# main_pcb.net
KiCad netlist of a schematic drawn in EAGLE
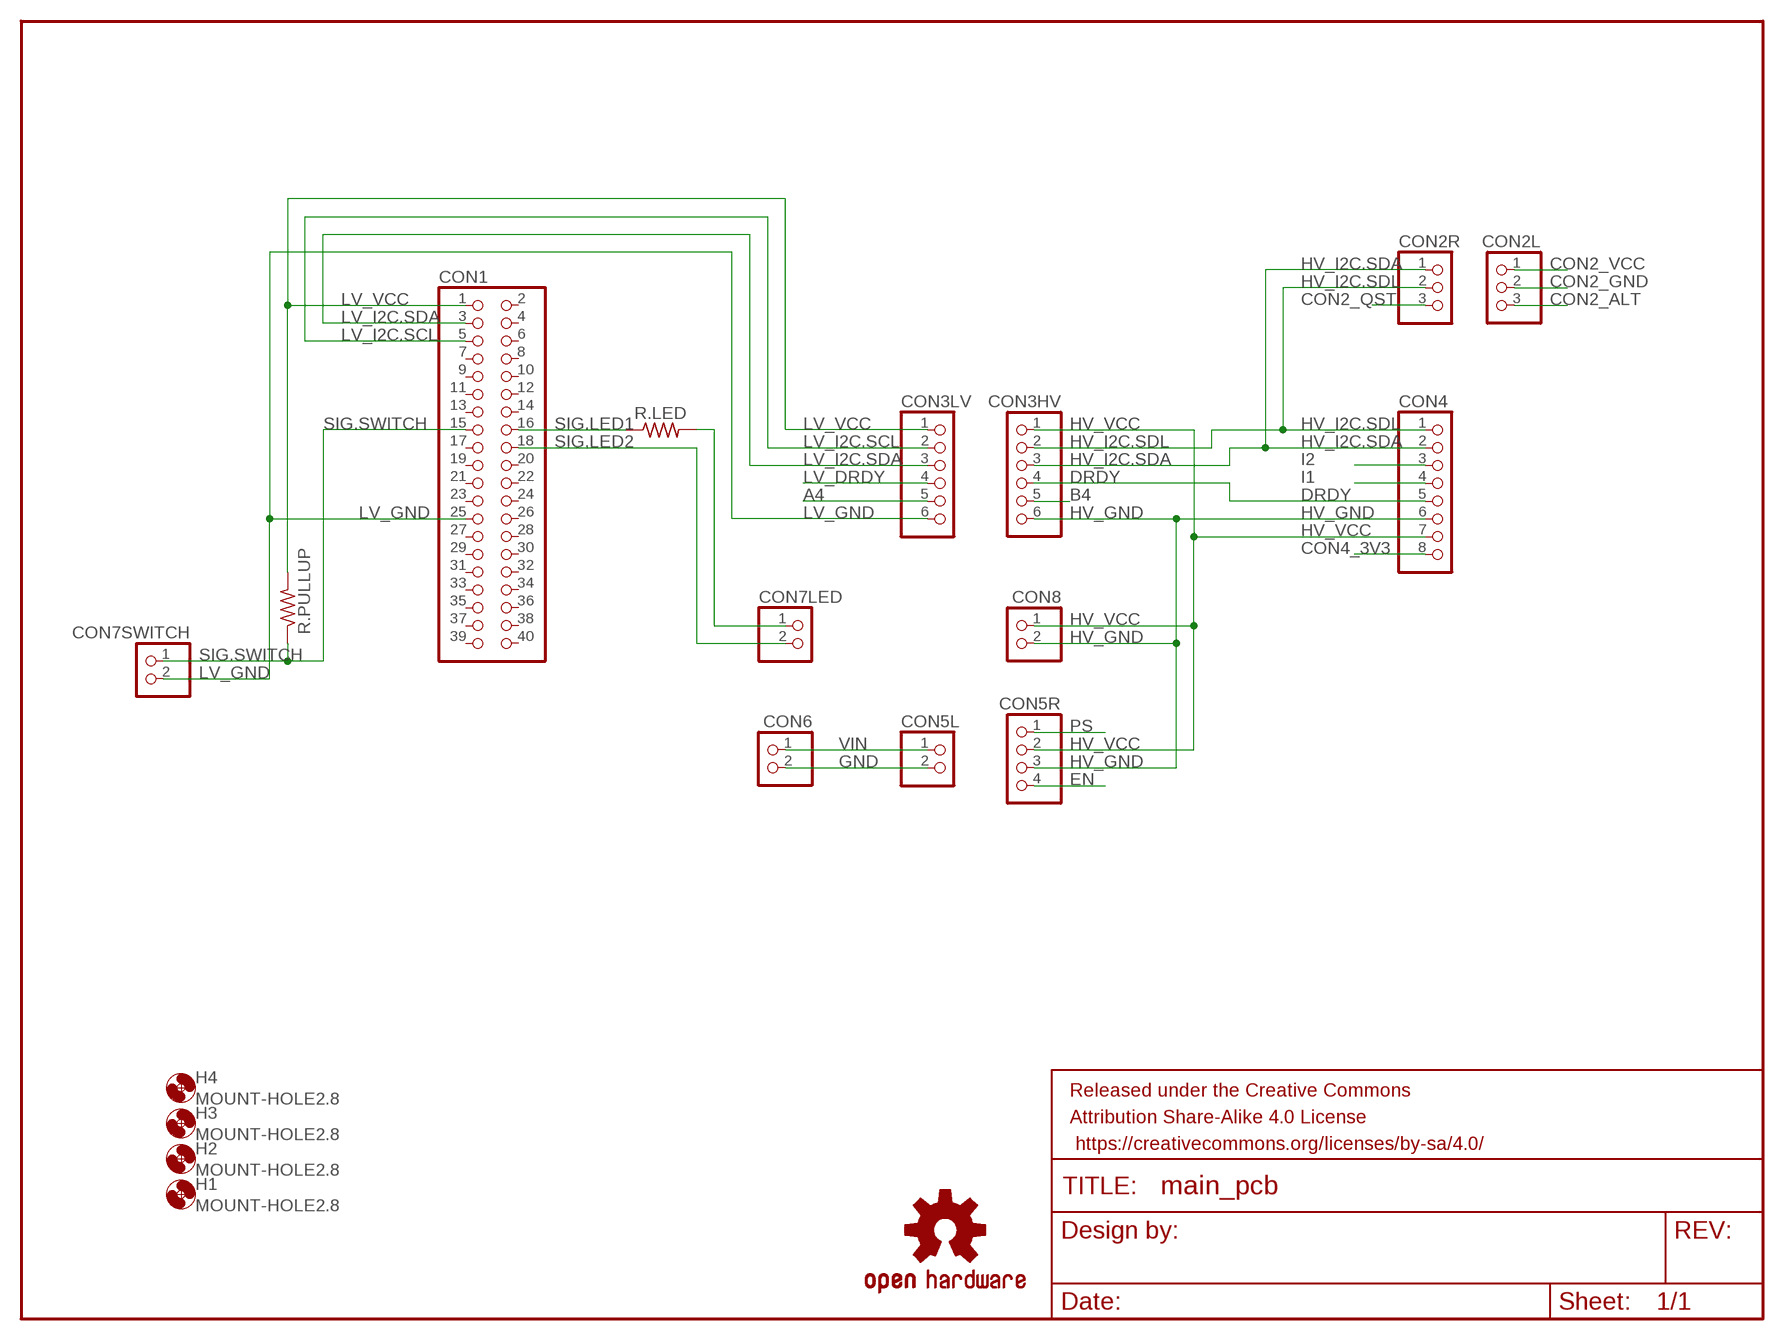
[diagram p0: schematic, sheet 1]

(export (version "E")
  (design (tool "Eeschema 10.0.6"))
  (components
    (comp (ref "CON1")
      (value "PINHD-2X20")
      (footprint "eagle-import:2X20")
      (libsource (lib "eagle-import") (part "PINHD-2X20"))
    )
    (comp (ref "CON2L")
      (value "PINHD-1X3")
      (footprint "eagle-import:1X03")
      (libsource (lib "eagle-import") (part "PINHD-1X3"))
    )
    (comp (ref "CON2R")
      (value "PINHD-1X3")
      (footprint "eagle-import:1X03")
      (libsource (lib "eagle-import") (part "PINHD-1X3"))
    )
    (comp (ref "CON3HV")
      (value "PINHD-1X6")
      (footprint "eagle-import:1X06")
      (libsource (lib "eagle-import") (part "PINHD-1X6"))
    )
    (comp (ref "CON3LV")
      (value "PINHD-1X6")
      (footprint "eagle-import:1X06")
      (libsource (lib "eagle-import") (part "PINHD-1X6"))
    )
    (comp (ref "CON4")
      (value "PINHD-1X8")
      (footprint "eagle-import:1X08")
      (libsource (lib "eagle-import") (part "PINHD-1X8"))
    )
    (comp (ref "CON5L")
      (value "PINHD-1X2")
      (footprint "eagle-import:1X02")
      (libsource (lib "eagle-import") (part "PINHD-1X2"))
    )
    (comp (ref "CON5R")
      (value "PINHD-1X4")
      (footprint "eagle-import:1X04")
      (libsource (lib "eagle-import") (part "PINHD-1X4"))
    )
    (comp (ref "CON6")
      (value "PINHD-1X2")
      (footprint "eagle-import:1X02")
      (libsource (lib "eagle-import") (part "PINHD-1X2"))
    )
    (comp (ref "CON7LED")
      (value "PINHD-1X2")
      (footprint "eagle-import:1X02")
      (libsource (lib "eagle-import") (part "PINHD-1X2"))
    )
    (comp (ref "CON7SWITCH")
      (value "PINHD-1X2")
      (footprint "eagle-import:1X02")
      (libsource (lib "eagle-import") (part "PINHD-1X2"))
    )
    (comp (ref "CON8")
      (value "PINHD-1X2")
      (footprint "eagle-import:1X02")
      (libsource (lib "eagle-import") (part "PINHD-1X2"))
    )
    (comp (ref "FRAME1")
      (value "FRAME-LETTER")
      (footprint "eagle-import:CREATIVE_COMMONS")
      (libsource (lib "eagle-import") (part "FRAME-LETTER"))
    )
    (comp (ref "H1")
      (value "MOUNT-HOLE2.8")
      (footprint "eagle-import:2,8")
      (libsource (lib "eagle-import") (part "MOUNT-HOLE2.8"))
    )
    (comp (ref "H2")
      (value "MOUNT-HOLE2.8")
      (footprint "eagle-import:2,8")
      (libsource (lib "eagle-import") (part "MOUNT-HOLE2.8"))
    )
    (comp (ref "H3")
      (value "MOUNT-HOLE2.8")
      (footprint "eagle-import:2,8")
      (libsource (lib "eagle-import") (part "MOUNT-HOLE2.8"))
    )
    (comp (ref "H4")
      (value "MOUNT-HOLE2.8")
      (footprint "eagle-import:2,8")
      (libsource (lib "eagle-import") (part "MOUNT-HOLE2.8"))
    )
    (comp (ref "LOGO1")
      (value "OSHW-LOGOL")
      (footprint "eagle-import:OSHW-LOGO-L")
      (libsource (lib "eagle-import") (part "OSHW-LOGOL"))
    )
    (comp (ref "R.LED")
      (value "R-US_0204/2V")
      (footprint "eagle-import:0204V")
      (libsource (lib "eagle-import") (part "R-US_0204/2V"))
    )
    (comp (ref "R.PULLUP")
      (value "R-US_0204/2V")
      (footprint "eagle-import:0204V")
      (libsource (lib "eagle-import") (part "R-US_0204/2V"))
    )
  )
  (nets
    (net (code "1") (name "/A4") (class "Default")
      (node (ref "CON3LV") (pin "5") (pinfunction "5_5") (pintype "passive"))
    )
    (net (code "2") (name "/B4") (class "Default")
      (node (ref "CON3HV") (pin "5") (pinfunction "5_5") (pintype "passive"))
    )
    (net (code "3") (name "/CON2_ALT") (class "Default")
      (node (ref "CON2L") (pin "3") (pinfunction "3_3") (pintype "passive"))
    )
    (net (code "4") (name "/CON2_GND") (class "Default")
      (node (ref "CON2L") (pin "2") (pinfunction "2_2") (pintype "passive"))
    )
    (net (code "5") (name "/CON2_QST") (class "Default")
      (node (ref "CON2R") (pin "3") (pinfunction "3_3") (pintype "passive"))
    )
    (net (code "6") (name "/CON2_VCC") (class "Default")
      (node (ref "CON2L") (pin "1") (pinfunction "1_1") (pintype "passive"))
    )
    (net (code "7") (name "/CON4_3V3") (class "Default")
      (node (ref "CON4") (pin "8") (pinfunction "8_8") (pintype "passive"))
    )
    (net (code "8") (name "/DRDY") (class "Default")
      (node (ref "CON3HV") (pin "4") (pinfunction "4_4") (pintype "passive"))
      (node (ref "CON4") (pin "5") (pinfunction "5_5") (pintype "passive"))
    )
    (net (code "9") (name "/EN") (class "Default")
      (node (ref "CON5R") (pin "4") (pinfunction "4_4") (pintype "passive"))
    )
    (net (code "10") (name "/GND") (class "Default")
      (node (ref "CON5L") (pin "2") (pinfunction "2_2") (pintype "passive"))
      (node (ref "CON6") (pin "2") (pinfunction "2_2") (pintype "passive"))
    )
    (net (code "11") (name "/HV_GND") (class "Default")
      (node (ref "CON3HV") (pin "6") (pinfunction "6_6") (pintype "passive"))
      (node (ref "CON4") (pin "6") (pinfunction "6_6") (pintype "passive"))
      (node (ref "CON5R") (pin "3") (pinfunction "3_3") (pintype "passive"))
      (node (ref "CON8") (pin "2") (pinfunction "2_2") (pintype "passive"))
    )
    (net (code "12") (name "/HV_I2C.SDA") (class "Default")
      (node (ref "CON2R") (pin "1") (pinfunction "1_1") (pintype "passive"))
      (node (ref "CON3HV") (pin "3") (pinfunction "3_3") (pintype "passive"))
      (node (ref "CON4") (pin "2") (pinfunction "2_2") (pintype "passive"))
    )
    (net (code "13") (name "/HV_I2C.SDL") (class "Default")
      (node (ref "CON2R") (pin "2") (pinfunction "2_2") (pintype "passive"))
      (node (ref "CON3HV") (pin "2") (pinfunction "2_2") (pintype "passive"))
      (node (ref "CON4") (pin "1") (pinfunction "1_1") (pintype "passive"))
    )
    (net (code "14") (name "/HV_VCC") (class "Default")
      (node (ref "CON3HV") (pin "1") (pinfunction "1_1") (pintype "passive"))
      (node (ref "CON4") (pin "7") (pinfunction "7_7") (pintype "passive"))
      (node (ref "CON5R") (pin "2") (pinfunction "2_2") (pintype "passive"))
      (node (ref "CON8") (pin "1") (pinfunction "1_1") (pintype "passive"))
    )
    (net (code "15") (name "/I1") (class "Default")
      (node (ref "CON4") (pin "4") (pinfunction "4_4") (pintype "passive"))
    )
    (net (code "16") (name "/I2") (class "Default")
      (node (ref "CON4") (pin "3") (pinfunction "3_3") (pintype "passive"))
    )
    (net (code "17") (name "/LV_DRDY") (class "Default")
      (node (ref "CON3LV") (pin "4") (pinfunction "4_4") (pintype "passive"))
    )
    (net (code "18") (name "/LV_GND") (class "Default")
      (node (ref "CON1") (pin "25") (pinfunction "25_25") (pintype "passive"))
      (node (ref "CON3LV") (pin "6") (pinfunction "6_6") (pintype "passive"))
      (node (ref "CON7SWITCH") (pin "2") (pinfunction "2_2") (pintype "passive"))
    )
    (net (code "19") (name "/LV_I2C.SCL") (class "Default")
      (node (ref "CON1") (pin "5") (pinfunction "5_5") (pintype "passive"))
      (node (ref "CON3LV") (pin "2") (pinfunction "2_2") (pintype "passive"))
    )
    (net (code "20") (name "/LV_I2C.SDA") (class "Default")
      (node (ref "CON1") (pin "3") (pinfunction "3_3") (pintype "passive"))
      (node (ref "CON3LV") (pin "3") (pinfunction "3_3") (pintype "passive"))
    )
    (net (code "21") (name "/LV_VCC") (class "Default")
      (node (ref "CON1") (pin "1") (pinfunction "1_1") (pintype "passive"))
      (node (ref "CON3LV") (pin "1") (pinfunction "1_1") (pintype "passive"))
      (node (ref "R.PULLUP") (pin "2") (pinfunction "2_2") (pintype "passive"))
    )
    (net (code "22") (name "/PS") (class "Default")
      (node (ref "CON5R") (pin "1") (pinfunction "1_1") (pintype "passive"))
    )
    (net (code "23") (name "/SIG.LED1") (class "Default")
      (node (ref "CON1") (pin "16") (pinfunction "16_16") (pintype "passive"))
      (node (ref "R.LED") (pin "1") (pinfunction "1_1") (pintype "passive"))
    )
    (net (code "24") (name "/SIG.LED2") (class "Default")
      (node (ref "CON1") (pin "18") (pinfunction "18_18") (pintype "passive"))
      (node (ref "CON7LED") (pin "2") (pinfunction "2_2") (pintype "passive"))
    )
    (net (code "25") (name "/SIG.SWITCH") (class "Default")
      (node (ref "CON1") (pin "15") (pinfunction "15_15") (pintype "passive"))
      (node (ref "CON7SWITCH") (pin "1") (pinfunction "1_1") (pintype "passive"))
      (node (ref "R.PULLUP") (pin "1") (pinfunction "1_1") (pintype "passive"))
    )
    (net (code "26") (name "/VIN") (class "Default")
      (node (ref "CON5L") (pin "1") (pinfunction "1_1") (pintype "passive"))
      (node (ref "CON6") (pin "1") (pinfunction "1_1") (pintype "passive"))
    )
    (net (code "27") (name "Net-(CON7LED-Pad1)") (class "Default")
      (node (ref "CON7LED") (pin "1") (pinfunction "1_1") (pintype "passive"))
      (node (ref "R.LED") (pin "2") (pinfunction "2_2") (pintype "passive"))
    )
    (net (code "28") (name "unconnected-(CON1-Pad2)") (class "Default")
      (node (ref "CON1") (pin "2") (pinfunction "2_2") (pintype "passive"))
    )
    (net (code "29") (name "unconnected-(CON1-Pad4)") (class "Default")
      (node (ref "CON1") (pin "4") (pinfunction "4_4") (pintype "passive"))
    )
    (net (code "30") (name "unconnected-(CON1-Pad6)") (class "Default")
      (node (ref "CON1") (pin "6") (pinfunction "6_6") (pintype "passive"))
    )
    (net (code "31") (name "unconnected-(CON1-Pad7)") (class "Default")
      (node (ref "CON1") (pin "7") (pinfunction "7_7") (pintype "passive"))
    )
    (net (code "32") (name "unconnected-(CON1-Pad8)") (class "Default")
      (node (ref "CON1") (pin "8") (pinfunction "8_8") (pintype "passive"))
    )
    (net (code "33") (name "unconnected-(CON1-Pad9)") (class "Default")
      (node (ref "CON1") (pin "9") (pinfunction "9_9") (pintype "passive"))
    )
    (net (code "34") (name "unconnected-(CON1-Pad10)") (class "Default")
      (node (ref "CON1") (pin "10") (pinfunction "10_10") (pintype "passive"))
    )
    (net (code "35") (name "unconnected-(CON1-Pad11)") (class "Default")
      (node (ref "CON1") (pin "11") (pinfunction "11_11") (pintype "passive"))
    )
    (net (code "36") (name "unconnected-(CON1-Pad12)") (class "Default")
      (node (ref "CON1") (pin "12") (pinfunction "12_12") (pintype "passive"))
    )
    (net (code "37") (name "unconnected-(CON1-Pad13)") (class "Default")
      (node (ref "CON1") (pin "13") (pinfunction "13_13") (pintype "passive"))
    )
    (net (code "38") (name "unconnected-(CON1-Pad14)") (class "Default")
      (node (ref "CON1") (pin "14") (pinfunction "14_14") (pintype "passive"))
    )
    (net (code "39") (name "unconnected-(CON1-Pad17)") (class "Default")
      (node (ref "CON1") (pin "17") (pinfunction "17_17") (pintype "passive"))
    )
    (net (code "40") (name "unconnected-(CON1-Pad19)") (class "Default")
      (node (ref "CON1") (pin "19") (pinfunction "19_19") (pintype "passive"))
    )
    (net (code "41") (name "unconnected-(CON1-Pad20)") (class "Default")
      (node (ref "CON1") (pin "20") (pinfunction "20_20") (pintype "passive"))
    )
    (net (code "42") (name "unconnected-(CON1-Pad21)") (class "Default")
      (node (ref "CON1") (pin "21") (pinfunction "21_21") (pintype "passive"))
    )
    (net (code "43") (name "unconnected-(CON1-Pad22)") (class "Default")
      (node (ref "CON1") (pin "22") (pinfunction "22_22") (pintype "passive"))
    )
    (net (code "44") (name "unconnected-(CON1-Pad23)") (class "Default")
      (node (ref "CON1") (pin "23") (pinfunction "23_23") (pintype "passive"))
    )
    (net (code "45") (name "unconnected-(CON1-Pad24)") (class "Default")
      (node (ref "CON1") (pin "24") (pinfunction "24_24") (pintype "passive"))
    )
    (net (code "46") (name "unconnected-(CON1-Pad26)") (class "Default")
      (node (ref "CON1") (pin "26") (pinfunction "26_26") (pintype "passive"))
    )
    (net (code "47") (name "unconnected-(CON1-Pad27)") (class "Default")
      (node (ref "CON1") (pin "27") (pinfunction "27_27") (pintype "passive"))
    )
    (net (code "48") (name "unconnected-(CON1-Pad28)") (class "Default")
      (node (ref "CON1") (pin "28") (pinfunction "28_28") (pintype "passive"))
    )
    (net (code "49") (name "unconnected-(CON1-Pad29)") (class "Default")
      (node (ref "CON1") (pin "29") (pinfunction "29_29") (pintype "passive"))
    )
    (net (code "50") (name "unconnected-(CON1-Pad30)") (class "Default")
      (node (ref "CON1") (pin "30") (pinfunction "30_30") (pintype "passive"))
    )
    (net (code "51") (name "unconnected-(CON1-Pad31)") (class "Default")
      (node (ref "CON1") (pin "31") (pinfunction "31_31") (pintype "passive"))
    )
    (net (code "52") (name "unconnected-(CON1-Pad32)") (class "Default")
      (node (ref "CON1") (pin "32") (pinfunction "32_32") (pintype "passive"))
    )
    (net (code "53") (name "unconnected-(CON1-Pad33)") (class "Default")
      (node (ref "CON1") (pin "33") (pinfunction "33_33") (pintype "passive"))
    )
    (net (code "54") (name "unconnected-(CON1-Pad34)") (class "Default")
      (node (ref "CON1") (pin "34") (pinfunction "34_34") (pintype "passive"))
    )
    (net (code "55") (name "unconnected-(CON1-Pad35)") (class "Default")
      (node (ref "CON1") (pin "35") (pinfunction "35_35") (pintype "passive"))
    )
    (net (code "56") (name "unconnected-(CON1-Pad36)") (class "Default")
      (node (ref "CON1") (pin "36") (pinfunction "36_36") (pintype "passive"))
    )
    (net (code "57") (name "unconnected-(CON1-Pad37)") (class "Default")
      (node (ref "CON1") (pin "37") (pinfunction "37_37") (pintype "passive"))
    )
    (net (code "58") (name "unconnected-(CON1-Pad38)") (class "Default")
      (node (ref "CON1") (pin "38") (pinfunction "38_38") (pintype "passive"))
    )
    (net (code "59") (name "unconnected-(CON1-Pad39)") (class "Default")
      (node (ref "CON1") (pin "39") (pinfunction "39_39") (pintype "passive"))
    )
    (net (code "60") (name "unconnected-(CON1-Pad40)") (class "Default")
      (node (ref "CON1") (pin "40") (pinfunction "40_40") (pintype "passive"))
    )
  )
)
